# 555.net
KiCad netlist of a schematic drawn in EAGLE
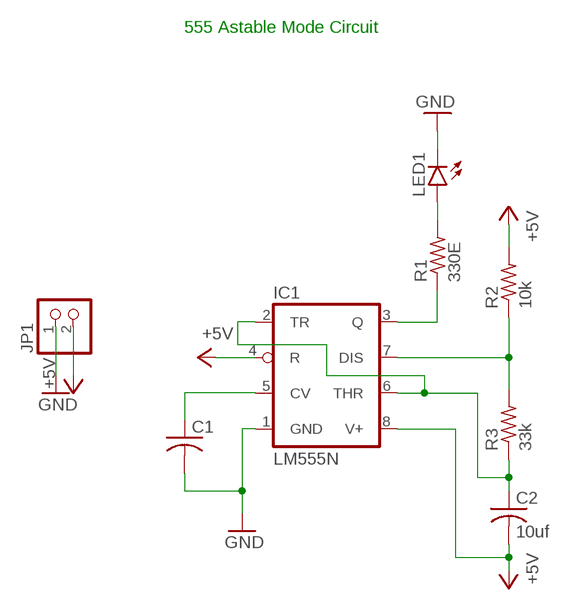
[diagram p0: schematic, sheet 1]

(export (version "E")
  (design (tool "Eeschema 10.0.6"))
  (components
    (comp (ref "C1")
      (value "C-US025-024X044")
      (footprint "eagle-import:C025-024X044")
      (libsource (lib "eagle-import") (part "C-US025-024X044"))
    )
    (comp (ref "C2")
      (value "10uf")
      (footprint "eagle-import:C025-024X044")
      (libsource (lib "eagle-import") (part "C-US025-024X044"))
    )
    (comp (ref "IC1")
      (value "LM555N")
      (footprint "eagle-import:DIL08-ROUND")
      (libsource (lib "eagle-import") (part "555NLM"))
    )
    (comp (ref "JP1")
      (value "PINHD-1X2")
      (footprint "eagle-import:1X02")
      (libsource (lib "eagle-import") (part "PINHD-1X2"))
    )
    (comp (ref "LED1")
      (value "LED5MM")
      (footprint "eagle-import:LED5MM")
      (libsource (lib "eagle-import") (part "LED5MM"))
    )
    (comp (ref "R1")
      (value "330E")
      (footprint "eagle-import:0204_7")
      (libsource (lib "eagle-import") (part "R-US_0204/7"))
    )
    (comp (ref "R2")
      (value "10k")
      (footprint "eagle-import:0204_7")
      (libsource (lib "eagle-import") (part "R-US_0204/7"))
    )
    (comp (ref "R3")
      (value "33k")
      (footprint "eagle-import:0204_7")
      (libsource (lib "eagle-import") (part "R-US_0204/7"))
    )
  )
  (nets
    (net (code "1") (name "+5V") (class "Default")
      (node (ref "C2") (pin "2") (pinfunction "2_2") (pintype "passive"))
      (node (ref "IC1") (pin "4") (pinfunction "R_4") (pintype "input"))
      (node (ref "IC1") (pin "8") (pinfunction "V+_8") (pintype "power_in"))
      (node (ref "JP1") (pin "2") (pinfunction "2_2") (pintype "passive"))
      (node (ref "R2") (pin "2") (pinfunction "2_2") (pintype "passive"))
    )
    (net (code "2") (name "GND") (class "Default")
      (node (ref "C1") (pin "2") (pinfunction "2_2") (pintype "passive"))
      (node (ref "IC1") (pin "1") (pinfunction "GND_1") (pintype "power_in"))
      (node (ref "JP1") (pin "1") (pinfunction "1_1") (pintype "passive"))
      (node (ref "LED1") (pin "K") (pinfunction "C_K") (pintype "passive"))
    )
    (net (code "3") (name "Net-(IC1-CV)") (class "Default")
      (node (ref "C1") (pin "1") (pinfunction "1_1") (pintype "passive"))
      (node (ref "IC1") (pin "5") (pinfunction "CV_5") (pintype "input"))
    )
    (net (code "4") (name "Net-(IC1-DIS)") (class "Default")
      (node (ref "IC1") (pin "7") (pinfunction "DIS_7") (pintype "input"))
      (node (ref "R2") (pin "1") (pinfunction "1_1") (pintype "passive"))
      (node (ref "R3") (pin "2") (pinfunction "2_2") (pintype "passive"))
    )
    (net (code "5") (name "Net-(IC1-Q)") (class "Default")
      (node (ref "IC1") (pin "3") (pinfunction "Q_3") (pintype "output"))
      (node (ref "R1") (pin "1") (pinfunction "1_1") (pintype "passive"))
    )
    (net (code "6") (name "Net-(IC1-THR)") (class "Default")
      (node (ref "C2") (pin "1") (pinfunction "1_1") (pintype "passive"))
      (node (ref "IC1") (pin "2") (pinfunction "TR_2") (pintype "input"))
      (node (ref "IC1") (pin "6") (pinfunction "THR_6") (pintype "input"))
      (node (ref "R3") (pin "1") (pinfunction "1_1") (pintype "passive"))
    )
    (net (code "7") (name "Net-(LED1-PadA)") (class "Default")
      (node (ref "LED1") (pin "A") (pinfunction "A_A") (pintype "passive"))
      (node (ref "R1") (pin "2") (pinfunction "2_2") (pintype "passive"))
    )
  )
)
